# AUX_power_board_V3_3.net
KiCad netlist of a schematic drawn in EAGLE
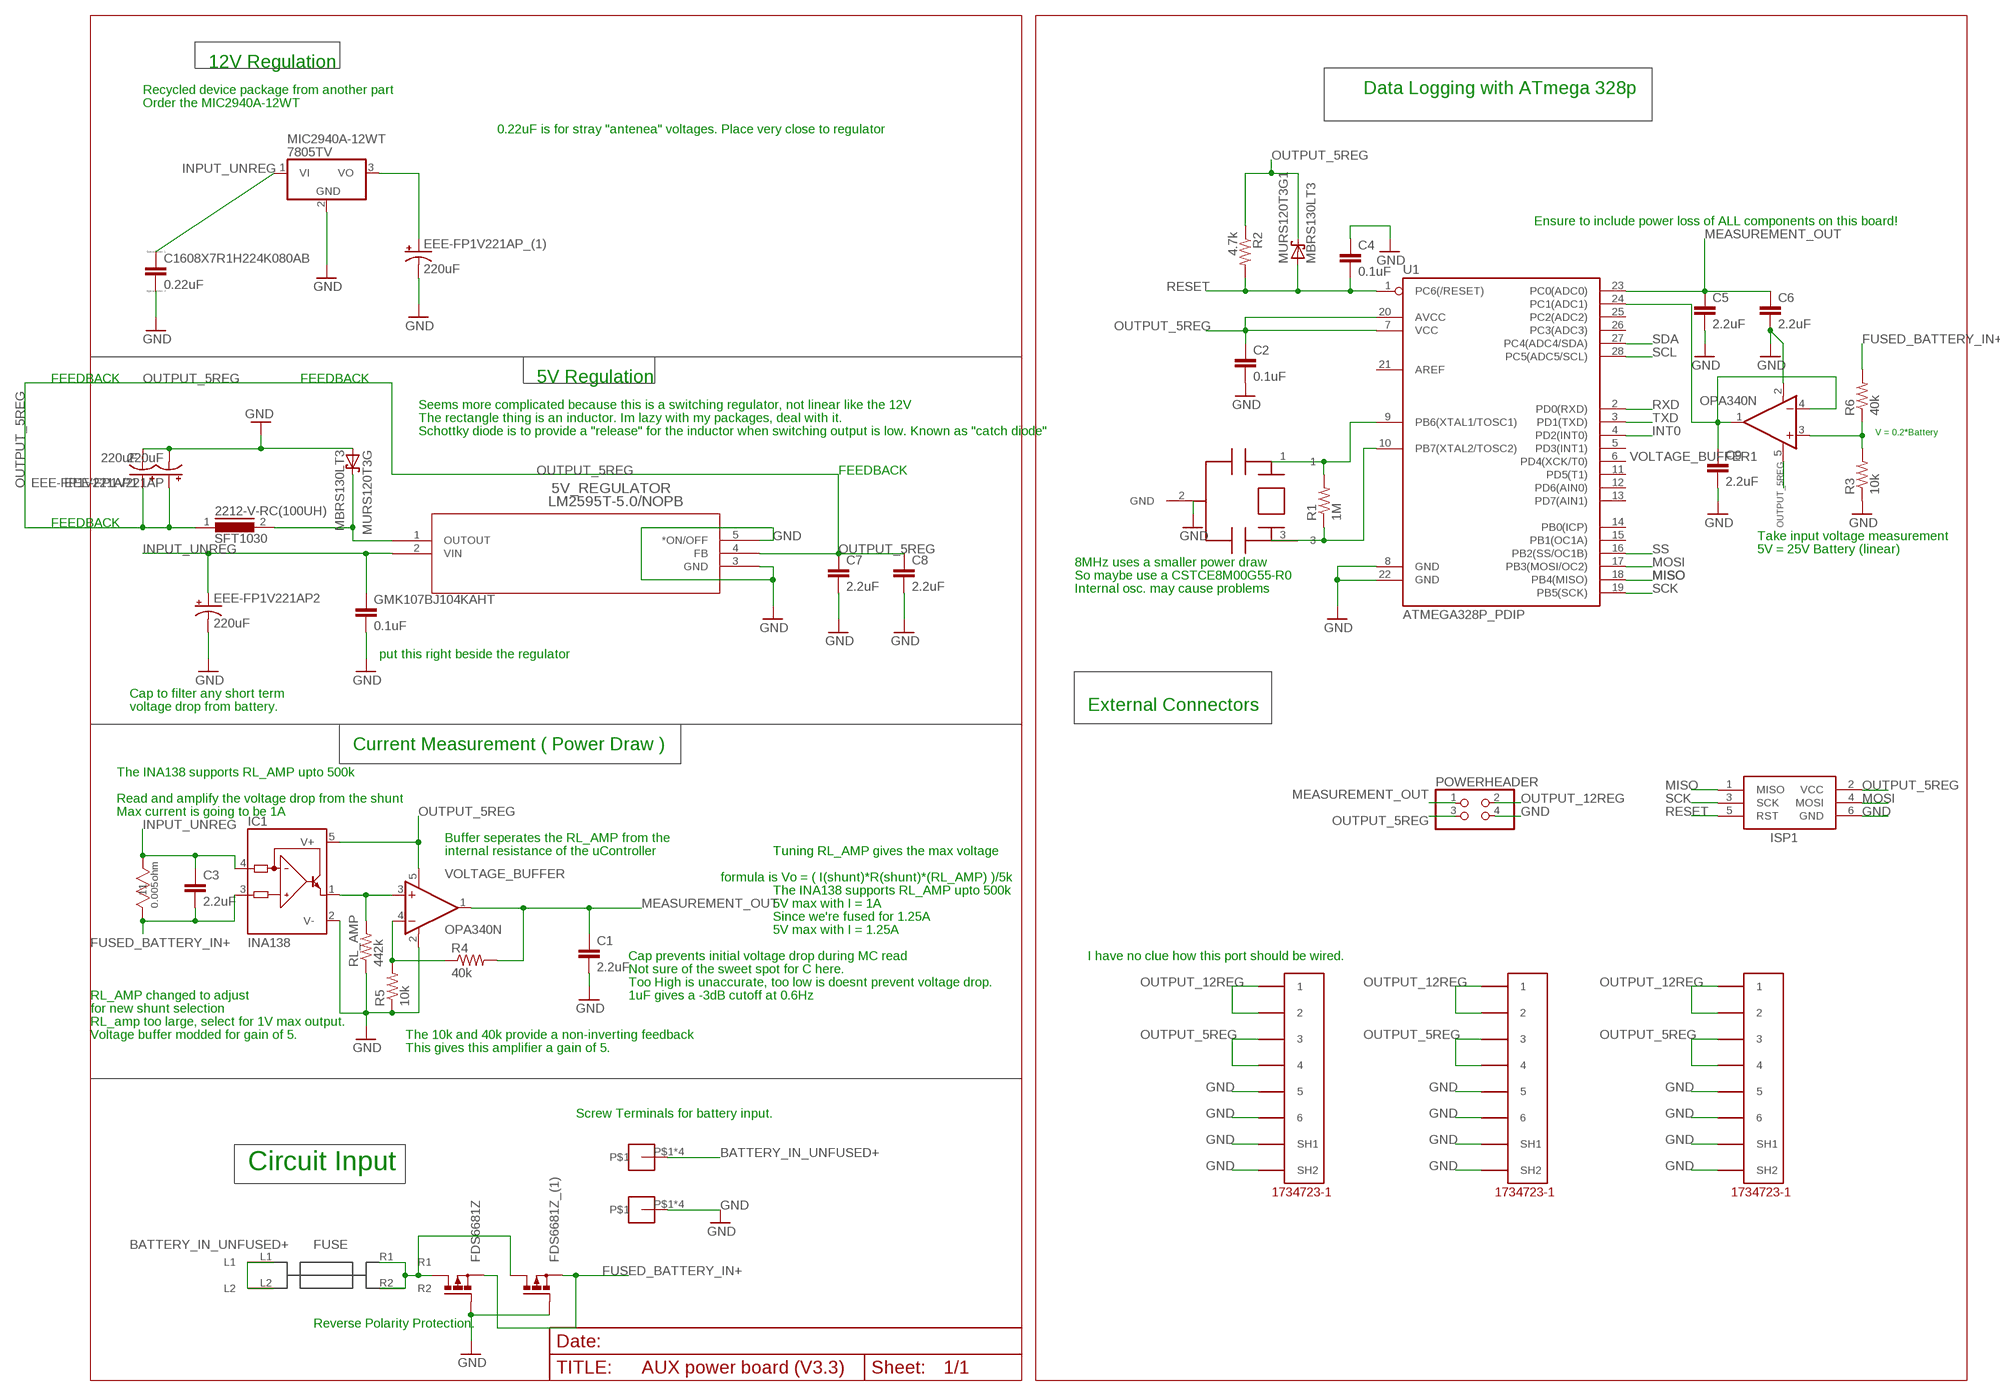
[diagram p0: schematic, sheet 1]

(export (version "E")
  (design (tool "Eeschema 10.0.6"))
  (components
    (comp (ref "5V_REGULATOR")
      (value "LM2595T-5.0/NOPB")
      (footprint "eagle-import:T05D")
      (fields
        (field (name "MANUFACTURER_PART_NUMBER") "LM2595T50")
        (field (name "COPYRIGHT") "Copyright C 2015 Accelerated Designs. All rights reserved")
      )
      (libsource (lib "eagle-import") (part "LM2595T-5.0/NOPB"))
    )
    (comp (ref "15FR005E")
      (value "15FR005E")
      (footprint "eagle-import:RES_15")
      (fields (field (name "COPYRIGHT") "Copyright C 2015 Accelerated Designs. All rights reserved"))
      (libsource (lib "eagle-import") (part "15FR005E"))
    )
    (comp (ref "2212-V-RC(100UH)")
      (value "SFT1030")
      (footprint "eagle-import:SFT1030")
      (libsource (lib "eagle-import") (part "SFT1030"))
    )
    (comp (ref "C1")
      (value "2.2uF")
      (footprint "eagle-import:C0603")
      (libsource (lib "eagle-import") (part "resistor_C-EUC0603"))
    )
    (comp (ref "C2")
      (value "0.1uF")
      (footprint "eagle-import:C0603")
      (libsource (lib "eagle-import") (part "resistor_C-EUC0603"))
    )
    (comp (ref "C3")
      (value "2.2uF")
      (footprint "eagle-import:C0603")
      (libsource (lib "eagle-import") (part "C-EUC0603"))
    )
    (comp (ref "C4")
      (value "0.1uF")
      (footprint "eagle-import:C0603")
      (libsource (lib "eagle-import") (part "C-EUC0603"))
    )
    (comp (ref "C5")
      (value "2.2uF")
      (footprint "eagle-import:C0603")
      (libsource (lib "eagle-import") (part "C-EUC0603"))
    )
    (comp (ref "C6")
      (value "2.2uF")
      (footprint "eagle-import:C0603")
      (libsource (lib "eagle-import") (part "C-EUC0603"))
    )
    (comp (ref "C7")
      (value "2.2uF")
      (footprint "eagle-import:C0603")
      (libsource (lib "eagle-import") (part "C-EUC0603"))
    )
    (comp (ref "C8")
      (value "2.2uF")
      (footprint "eagle-import:C0603")
      (libsource (lib "eagle-import") (part "C-EUC0603"))
    )
    (comp (ref "C9")
      (value "2.2uF")
      (footprint "eagle-import:C0603")
      (libsource (lib "eagle-import") (part "C-EUC0603"))
    )
    (comp (ref "C1608X7R1H224K080AB")
      (value "0.22uF")
      (footprint "eagle-import:C0603")
      (libsource (lib "eagle-import") (part "CC0603"))
    )
    (comp (ref "CSTCE8M00G55-R0")
      (value "CSTCE16M0V53-R0")
      (footprint "eagle-import:RESONATOR")
      (libsource (lib "eagle-import") (part "CSTCE16M0V53-R0"))
    )
    (comp (ref "EEE-FP1V221AP")
      (value "220uF")
      (footprint "eagle-import:175TMP-0808")
      (libsource (lib "eagle-import") (part "CPOL-US175TMP-0808"))
    )
    (comp (ref "EEE-FP1V221AP1")
      (value "220uF")
      (footprint "eagle-import:175TMP-0808")
      (libsource (lib "eagle-import") (part "CPOL-US175TMP-0808"))
    )
    (comp (ref "EEE-FP1V221AP2")
      (value "220uF")
      (footprint "eagle-import:175TMP-0808")
      (libsource (lib "eagle-import") (part "CPOL-US175TMP-0808"))
    )
    (comp (ref "EEE-FP1V221AP_(1)")
      (value "220uF")
      (footprint "eagle-import:175TMP-0808")
      (libsource (lib "eagle-import") (part "CPOL-US175TMP-0808"))
    )
    (comp (ref "FDS6681Z")
      (value "P-MOSFET-SO8")
      (footprint "eagle-import:SO-08")
      (libsource (lib "eagle-import") (part "P-MOSFET-SO8"))
    )
    (comp (ref "FDS6681Z_(1)")
      (value "P-MOSFET-SO8")
      (footprint "eagle-import:SO-08")
      (libsource (lib "eagle-import") (part "P-MOSFET-SO8"))
    )
    (comp (ref "GMK107BJ104KAHT")
      (value "0.1uF")
      (footprint "eagle-import:C0603")
      (libsource (lib "eagle-import") (part "C-EUC0603"))
    )
    (comp (ref "IC1")
      (value "INA138")
      (footprint "eagle-import:SOT23-5")
      (fields (field (name "MF") "TEXAS INSTRUMENTS") (field (name "MPN") "INA138NA/250"))
      (libsource (lib "eagle-import") (part "INA138"))
    )
    (comp (ref "ISP1")
      (value "AVRISP-6")
      (footprint "eagle-import:AVRISP")
      (libsource (lib "eagle-import") (part "AVRISP-6"))
    )
    (comp (ref "MIC2940A-12WT")
      (value "7805TV")
      (footprint "eagle-import:TO220V")
      (libsource (lib "eagle-import") (part "78TV05"))
    )
    (comp (ref "MINIBLADE")
      (value "3568")
      (footprint "eagle-import:3568")
      (libsource (lib "eagle-import") (part "3568"))
    )
    (comp (ref "MURS120T3G")
      (value "MBRS130LT3")
      (footprint "eagle-import:SMB")
      (libsource (lib "eagle-import") (part "MBRS130LT3"))
    )
    (comp (ref "MURS120T3G1")
      (value "MBRS130LT3")
      (footprint "eagle-import:SMB")
      (libsource (lib "eagle-import") (part "MBRS130LT3"))
    )
    (comp (ref "POWERHEADER")
      (value "PINHD-2X2")
      (footprint "eagle-import:2X02")
      (libsource (lib "eagle-import") (part "PINHD-2X2"))
    )
    (comp (ref "R1")
      (value "1M")
      (footprint "eagle-import:R0603")
      (libsource (lib "eagle-import") (part "R-US_R0603"))
    )
    (comp (ref "R2")
      (value "4.7k")
      (footprint "eagle-import:R0603")
      (libsource (lib "eagle-import") (part "resistor_R-US_R0603"))
    )
    (comp (ref "R3")
      (value "10k")
      (footprint "eagle-import:R0603")
      (libsource (lib "eagle-import") (part "resistor_R-US_R0603"))
    )
    (comp (ref "R4")
      (value "40k")
      (footprint "eagle-import:R0603")
      (libsource (lib "eagle-import") (part "resistor_R-US_R0603"))
    )
    (comp (ref "R5")
      (value "10k")
      (footprint "eagle-import:R0603")
      (libsource (lib "eagle-import") (part "resistor_R-US_R0603"))
    )
    (comp (ref "R6")
      (value "40k")
      (footprint "eagle-import:R0603")
      (libsource (lib "eagle-import") (part "resistor_R-US_R0603"))
    )
    (comp (ref "RL_AMP")
      (value "442k")
      (footprint "eagle-import:R0603")
      (libsource (lib "eagle-import") (part "resistor_R-US_R0603"))
    )
    (comp (ref "U$3")
      (value "5555140-6")
      (footprint "eagle-import:1734723-1_RJ11")
      (libsource (lib "eagle-import") (part "5555140-6"))
    )
    (comp (ref "U$4")
      (value "5555140-6")
      (footprint "eagle-import:1734723-1_RJ11")
      (libsource (lib "eagle-import") (part "5555140-6"))
    )
    (comp (ref "U$5")
      (value "5555140-6")
      (footprint "eagle-import:1734723-1_RJ11")
      (libsource (lib "eagle-import") (part "5555140-6"))
    )
    (comp (ref "U$6")
      (value "SCREW-8191")
      (footprint "eagle-import:SCREW-8191")
      (libsource (lib "eagle-import") (part "SCREW-8191"))
    )
    (comp (ref "U$7")
      (value "SCREW-8191")
      (footprint "eagle-import:SCREW-8191")
      (libsource (lib "eagle-import") (part "SCREW-8191"))
    )
    (comp (ref "U1")
      (value "ATMEGA328P_PDIP")
      (footprint "eagle-import:DIL28-3")
      (libsource (lib "eagle-import") (part "ATMEGA328P_PDIP"))
    )
    (comp (ref "VOLTAGE_BUFFER")
      (value "OPA340N")
      (footprint "eagle-import:SOT23-5")
      (fields (field (name "MPN") "OPA340NA/3KG4"))
      (libsource (lib "eagle-import") (part "OPA340N"))
    )
    (comp (ref "VOLTAGE_BUFFER1")
      (value "OPA340N")
      (footprint "eagle-import:SOT23-5")
      (fields (field (name "MPN") "OPA340NA/3KG4"))
      (libsource (lib "eagle-import") (part "OPA340N"))
    )
  )
  (nets
    (net (code "1") (name "/BATTERY_IN_UNFUSED+") (class "Default")
      (node (ref "MINIBLADE") (pin "L1") (pinfunction "L1_L1") (pintype "bidirectional"))
      (node (ref "MINIBLADE") (pin "L2") (pinfunction "L2_L2") (pintype "bidirectional"))
      (node (ref "U$6") (pin "P$1") (pinfunction "P$1_P$1") (pintype "bidirectional"))
      (node (ref "U$6") (pin "P$2") (pinfunction "P$1_P$2") (pintype "bidirectional"))
      (node (ref "U$6") (pin "P$3") (pinfunction "P$1_P$3") (pintype "bidirectional"))
      (node (ref "U$6") (pin "P$4") (pinfunction "P$1_P$4") (pintype "bidirectional"))
    )
    (net (code "2") (name "/FUSED_BATTERY_IN+") (class "Default")
      (node (ref "15FR005E") (pin "1") (pinfunction "11_1") (pintype "passive"))
      (node (ref "C3") (pin "2") (pinfunction "2_2") (pintype "passive"))
      (node (ref "FDS6681Z") (pin "1") (pinfunction "S_1") (pintype "passive"))
      (node (ref "FDS6681Z") (pin "2") (pinfunction "S_2") (pintype "passive"))
      (node (ref "FDS6681Z") (pin "3") (pinfunction "S_3") (pintype "passive"))
      (node (ref "FDS6681Z_(1)") (pin "1") (pinfunction "S_1") (pintype "passive"))
      (node (ref "FDS6681Z_(1)") (pin "2") (pinfunction "S_2") (pintype "passive"))
      (node (ref "FDS6681Z_(1)") (pin "3") (pinfunction "S_3") (pintype "passive"))
      (node (ref "IC1") (pin "3") (pinfunction "IN+_3") (pintype "input"))
      (node (ref "R6") (pin "2") (pinfunction "2_2") (pintype "passive"))
    )
    (net (code "3") (name "/INPUT_UNREG") (class "Default")
      (node (ref "15FR005E") (pin "2") (pinfunction "22_2") (pintype "passive"))
      (node (ref "5V_REGULATOR") (pin "2") (pinfunction "VIN_2") (pintype "input"))
      (node (ref "C1608X7R1H224K080AB") (pin "1") (pinfunction "1_1") (pintype "passive"))
      (node (ref "C3") (pin "1") (pinfunction "1_1") (pintype "passive"))
      (node (ref "EEE-FP1V221AP2") (pin "+") (pinfunction "+_+") (pintype "passive"))
      (node (ref "GMK107BJ104KAHT") (pin "1") (pinfunction "1_1") (pintype "passive"))
      (node (ref "IC1") (pin "4") (pinfunction "IN-_4") (pintype "input"))
      (node (ref "MIC2940A-12WT") (pin "1") (pinfunction "VI_1") (pintype "input"))
    )
    (net (code "4") (name "/INT0") (class "Default")
      (node (ref "U1") (pin "4") (pinfunction "PD2(INT0)_4") (pintype "bidirectional"))
    )
    (net (code "5") (name "/MEASUREMENT_OUT") (class "Default")
      (node (ref "C1") (pin "1") (pinfunction "1_1") (pintype "passive"))
      (node (ref "C5") (pin "1") (pinfunction "1_1") (pintype "passive"))
      (node (ref "C6") (pin "1") (pinfunction "1_1") (pintype "passive"))
      (node (ref "POWERHEADER") (pin "1") (pinfunction "1_1") (pintype "passive"))
      (node (ref "R4") (pin "2") (pinfunction "2_2") (pintype "passive"))
      (node (ref "U1") (pin "23") (pinfunction "PC0(ADC0)_23") (pintype "bidirectional"))
      (node (ref "VOLTAGE_BUFFER") (pin "1") (pinfunction "OUT_1") (pintype "output"))
    )
    (net (code "6") (name "/MISO") (class "Default")
      (node (ref "ISP1") (pin "1") (pinfunction "MISO_1") (pintype "input"))
      (node (ref "U1") (pin "18") (pinfunction "PB4(MISO)_18") (pintype "bidirectional"))
    )
    (net (code "7") (name "/MOSI") (class "Default")
      (node (ref "ISP1") (pin "4") (pinfunction "MOSI_4") (pintype "output"))
      (node (ref "U1") (pin "17") (pinfunction "PB3(MOSI/OC2)_17") (pintype "bidirectional"))
    )
    (net (code "8") (name "/OUTPUT_5REG") (class "Default")
      (node (ref "2212-V-RC(100UH)") (pin "1") (pinfunction "1_1") (pintype "passive"))
      (node (ref "5V_REGULATOR") (pin "4") (pinfunction "FB_4") (pintype "passive"))
      (node (ref "C2") (pin "1") (pinfunction "1_1") (pintype "passive"))
      (node (ref "C7") (pin "1") (pinfunction "1_1") (pintype "passive"))
      (node (ref "C8") (pin "1") (pinfunction "1_1") (pintype "passive"))
      (node (ref "EEE-FP1V221AP") (pin "+") (pinfunction "+_+") (pintype "passive"))
      (node (ref "EEE-FP1V221AP1") (pin "+") (pinfunction "+_+") (pintype "passive"))
      (node (ref "IC1") (pin "5") (pinfunction "V+_5") (pintype "power_in"))
      (node (ref "ISP1") (pin "2") (pinfunction "VCC_2") (pintype "power_in"))
      (node (ref "MURS120T3G1") (pin "C") (pinfunction "C_C") (pintype "passive"))
      (node (ref "POWERHEADER") (pin "3") (pinfunction "3_3") (pintype "passive"))
      (node (ref "R2") (pin "1") (pinfunction "1_1") (pintype "passive"))
      (node (ref "U$3") (pin "3") (pinfunction "3_3") (pintype "bidirectional"))
      (node (ref "U$3") (pin "4") (pinfunction "4_4") (pintype "bidirectional"))
      (node (ref "U$4") (pin "3") (pinfunction "3_3") (pintype "bidirectional"))
      (node (ref "U$4") (pin "4") (pinfunction "4_4") (pintype "bidirectional"))
      (node (ref "U$5") (pin "3") (pinfunction "3_3") (pintype "bidirectional"))
      (node (ref "U$5") (pin "4") (pinfunction "4_4") (pintype "bidirectional"))
      (node (ref "U1") (pin "20") (pinfunction "AVCC_20") (pintype "bidirectional"))
      (node (ref "U1") (pin "7") (pinfunction "VCC_7") (pintype "bidirectional"))
      (node (ref "VOLTAGE_BUFFER") (pin "5") (pinfunction "V+_5") (pintype "power_in"))
      (node (ref "VOLTAGE_BUFFER1") (pin "5") (pinfunction "V+_5") (pintype "power_in"))
    )
    (net (code "9") (name "/OUTPUT_12REG") (class "Default")
      (node (ref "EEE-FP1V221AP_(1)") (pin "+") (pinfunction "+_+") (pintype "passive"))
      (node (ref "MIC2940A-12WT") (pin "3") (pinfunction "VO_3") (pintype "passive"))
      (node (ref "POWERHEADER") (pin "2") (pinfunction "2_2") (pintype "passive"))
      (node (ref "U$3") (pin "1") (pinfunction "1_1") (pintype "bidirectional"))
      (node (ref "U$3") (pin "2") (pinfunction "2_2") (pintype "bidirectional"))
      (node (ref "U$4") (pin "1") (pinfunction "1_1") (pintype "bidirectional"))
      (node (ref "U$4") (pin "2") (pinfunction "2_2") (pintype "bidirectional"))
      (node (ref "U$5") (pin "1") (pinfunction "1_1") (pintype "bidirectional"))
      (node (ref "U$5") (pin "2") (pinfunction "2_2") (pintype "bidirectional"))
    )
    (net (code "10") (name "/RESET") (class "Default")
      (node (ref "C4") (pin "2") (pinfunction "2_2") (pintype "passive"))
      (node (ref "ISP1") (pin "5") (pinfunction "RST_5") (pintype "output"))
      (node (ref "MURS120T3G1") (pin "A") (pinfunction "A_A") (pintype "passive"))
      (node (ref "R2") (pin "2") (pinfunction "2_2") (pintype "passive"))
      (node (ref "U1") (pin "1") (pinfunction "PC6(/RESET)_1") (pintype "bidirectional"))
    )
    (net (code "11") (name "/RXD") (class "Default")
      (node (ref "U1") (pin "2") (pinfunction "PD0(RXD)_2") (pintype "bidirectional"))
    )
    (net (code "12") (name "/SCK") (class "Default")
      (node (ref "ISP1") (pin "3") (pinfunction "SCK_3") (pintype "output"))
      (node (ref "U1") (pin "19") (pinfunction "PB5(SCK)_19") (pintype "bidirectional"))
    )
    (net (code "13") (name "/SCL") (class "Default")
      (node (ref "U1") (pin "28") (pinfunction "PC5(ADC5/SCL)_28") (pintype "bidirectional"))
    )
    (net (code "14") (name "/SDA") (class "Default")
      (node (ref "U1") (pin "27") (pinfunction "PC4(ADC4/SDA)_27") (pintype "bidirectional"))
    )
    (net (code "15") (name "/SS") (class "Default")
      (node (ref "U1") (pin "16") (pinfunction "PB2(SS/OC1B)_16") (pintype "bidirectional"))
    )
    (net (code "16") (name "/TXD") (class "Default")
      (node (ref "U1") (pin "3") (pinfunction "PD1(TXD)_3") (pintype "bidirectional"))
    )
    (net (code "17") (name "GND") (class "Default")
      (node (ref "5V_REGULATOR") (pin "3") (pinfunction "GND_3") (pintype "passive"))
      (node (ref "5V_REGULATOR") (pin "5") (pinfunction "*ON/OFF_5") (pintype "passive"))
      (node (ref "C1") (pin "2") (pinfunction "2_2") (pintype "passive"))
      (node (ref "C1608X7R1H224K080AB") (pin "2") (pinfunction "2_2") (pintype "passive"))
      (node (ref "C2") (pin "2") (pinfunction "2_2") (pintype "passive"))
      (node (ref "C4") (pin "1") (pinfunction "1_1") (pintype "passive"))
      (node (ref "C5") (pin "2") (pinfunction "2_2") (pintype "passive"))
      (node (ref "C6") (pin "2") (pinfunction "2_2") (pintype "passive"))
      (node (ref "C7") (pin "2") (pinfunction "2_2") (pintype "passive"))
      (node (ref "C8") (pin "2") (pinfunction "2_2") (pintype "passive"))
      (node (ref "C9") (pin "2") (pinfunction "2_2") (pintype "passive"))
      (node (ref "CSTCE8M00G55-R0") (pin "2") (pinfunction "GND_2") (pintype "bidirectional"))
      (node (ref "EEE-FP1V221AP") (pin "-") (pinfunction "-_-") (pintype "passive"))
      (node (ref "EEE-FP1V221AP1") (pin "-") (pinfunction "-_-") (pintype "passive"))
      (node (ref "EEE-FP1V221AP2") (pin "-") (pinfunction "-_-") (pintype "passive"))
      (node (ref "EEE-FP1V221AP_(1)") (pin "-") (pinfunction "-_-") (pintype "passive"))
      (node (ref "FDS6681Z") (pin "4") (pinfunction "G_4") (pintype "passive"))
      (node (ref "FDS6681Z_(1)") (pin "4") (pinfunction "G_4") (pintype "passive"))
      (node (ref "GMK107BJ104KAHT") (pin "2") (pinfunction "2_2") (pintype "passive"))
      (node (ref "IC1") (pin "2") (pinfunction "V-_2") (pintype "power_in"))
      (node (ref "ISP1") (pin "6") (pinfunction "GND_6") (pintype "power_in"))
      (node (ref "MIC2940A-12WT") (pin "2") (pinfunction "GND_2") (pintype "passive"))
      (node (ref "MURS120T3G") (pin "A") (pinfunction "A_A") (pintype "passive"))
      (node (ref "POWERHEADER") (pin "4") (pinfunction "4_4") (pintype "passive"))
      (node (ref "R3") (pin "1") (pinfunction "1_1") (pintype "passive"))
      (node (ref "R5") (pin "1") (pinfunction "1_1") (pintype "passive"))
      (node (ref "RL_AMP") (pin "1") (pinfunction "1_1") (pintype "passive"))
      (node (ref "U$3") (pin "5") (pinfunction "5_5") (pintype "bidirectional"))
      (node (ref "U$3") (pin "6") (pinfunction "6_6") (pintype "bidirectional"))
      (node (ref "U$3") (pin "SH1") (pinfunction "SH1_SH1") (pintype "bidirectional"))
      (node (ref "U$3") (pin "SH2") (pinfunction "SH2_SH2") (pintype "bidirectional"))
      (node (ref "U$4") (pin "5") (pinfunction "5_5") (pintype "bidirectional"))
      (node (ref "U$4") (pin "6") (pinfunction "6_6") (pintype "bidirectional"))
      (node (ref "U$4") (pin "SH1") (pinfunction "SH1_SH1") (pintype "bidirectional"))
      (node (ref "U$4") (pin "SH2") (pinfunction "SH2_SH2") (pintype "bidirectional"))
      (node (ref "U$5") (pin "5") (pinfunction "5_5") (pintype "bidirectional"))
      (node (ref "U$5") (pin "6") (pinfunction "6_6") (pintype "bidirectional"))
      (node (ref "U$5") (pin "SH1") (pinfunction "SH1_SH1") (pintype "bidirectional"))
      (node (ref "U$5") (pin "SH2") (pinfunction "SH2_SH2") (pintype "bidirectional"))
      (node (ref "U$7") (pin "P$1") (pinfunction "P$1_P$1") (pintype "bidirectional"))
      (node (ref "U$7") (pin "P$2") (pinfunction "P$1_P$2") (pintype "bidirectional"))
      (node (ref "U$7") (pin "P$3") (pinfunction "P$1_P$3") (pintype "bidirectional"))
      (node (ref "U$7") (pin "P$4") (pinfunction "P$1_P$4") (pintype "bidirectional"))
      (node (ref "U1") (pin "22") (pinfunction "GND_22") (pintype "bidirectional"))
      (node (ref "U1") (pin "8") (pinfunction "GND_8") (pintype "bidirectional"))
      (node (ref "VOLTAGE_BUFFER") (pin "2") (pinfunction "V-_2") (pintype "power_in"))
      (node (ref "VOLTAGE_BUFFER1") (pin "2") (pinfunction "V-_2") (pintype "power_in"))
    )
    (net (code "18") (name "Net-(5V_REGULATOR-OUTOUT)") (class "Default")
      (node (ref "2212-V-RC(100UH)") (pin "2") (pinfunction "2_2") (pintype "passive"))
      (node (ref "5V_REGULATOR") (pin "1") (pinfunction "OUTOUT_1") (pintype "output"))
      (node (ref "MURS120T3G") (pin "C") (pinfunction "C_C") (pintype "passive"))
    )
    (net (code "19") (name "Net-(FDS6681Z-D-Pad5)") (class "Default")
      (node (ref "FDS6681Z") (pin "5") (pinfunction "D_5") (pintype "passive"))
      (node (ref "FDS6681Z") (pin "6") (pinfunction "D_6") (pintype "passive"))
      (node (ref "FDS6681Z") (pin "7") (pinfunction "D_7") (pintype "passive"))
      (node (ref "FDS6681Z") (pin "8") (pinfunction "D_8") (pintype "passive"))
      (node (ref "FDS6681Z_(1)") (pin "5") (pinfunction "D_5") (pintype "passive"))
      (node (ref "FDS6681Z_(1)") (pin "6") (pinfunction "D_6") (pintype "passive"))
      (node (ref "FDS6681Z_(1)") (pin "7") (pinfunction "D_7") (pintype "passive"))
      (node (ref "FDS6681Z_(1)") (pin "8") (pinfunction "D_8") (pintype "passive"))
      (node (ref "MINIBLADE") (pin "R1") (pinfunction "R1_R1") (pintype "bidirectional"))
      (node (ref "MINIBLADE") (pin "R2") (pinfunction "R2_R2") (pintype "bidirectional"))
    )
    (net (code "20") (name "Net-(IC1-OUT)") (class "Default")
      (node (ref "IC1") (pin "1") (pinfunction "OUT_1") (pintype "output"))
      (node (ref "RL_AMP") (pin "2") (pinfunction "2_2") (pintype "passive"))
      (node (ref "VOLTAGE_BUFFER") (pin "3") (pinfunction "+IN_3") (pintype "input"))
    )
    (net (code "21") (name "Net-(U1-PB6(XTAL1{slash}TOSC1))") (class "Default")
      (node (ref "CSTCE8M00G55-R0") (pin "1") (pinfunction "1_1") (pintype "bidirectional"))
      (node (ref "R1") (pin "2") (pinfunction "2_2") (pintype "passive"))
      (node (ref "U1") (pin "9") (pinfunction "PB6(XTAL1/TOSC1)_9") (pintype "bidirectional"))
    )
    (net (code "22") (name "Net-(U1-PB7(XTAL2{slash}TOSC2))") (class "Default")
      (node (ref "CSTCE8M00G55-R0") (pin "3") (pinfunction "3_3") (pintype "bidirectional"))
      (node (ref "R1") (pin "1") (pinfunction "1_1") (pintype "passive"))
      (node (ref "U1") (pin "10") (pinfunction "PB7(XTAL2/TOSC2)_10") (pintype "bidirectional"))
    )
    (net (code "23") (name "Net-(U1-PC1(ADC1))") (class "Default")
      (node (ref "C9") (pin "1") (pinfunction "1_1") (pintype "passive"))
      (node (ref "U1") (pin "24") (pinfunction "PC1(ADC1)_24") (pintype "bidirectional"))
      (node (ref "VOLTAGE_BUFFER1") (pin "1") (pinfunction "OUT_1") (pintype "output"))
      (node (ref "VOLTAGE_BUFFER1") (pin "4") (pinfunction "-IN_4") (pintype "input"))
    )
    (net (code "24") (name "Net-(VOLTAGE_BUFFER--IN)") (class "Default")
      (node (ref "R4") (pin "1") (pinfunction "1_1") (pintype "passive"))
      (node (ref "R5") (pin "2") (pinfunction "2_2") (pintype "passive"))
      (node (ref "VOLTAGE_BUFFER") (pin "4") (pinfunction "-IN_4") (pintype "input"))
    )
    (net (code "25") (name "Net-(VOLTAGE_BUFFER1-+IN)") (class "Default")
      (node (ref "R3") (pin "2") (pinfunction "2_2") (pintype "passive"))
      (node (ref "R6") (pin "1") (pinfunction "1_1") (pintype "passive"))
      (node (ref "VOLTAGE_BUFFER1") (pin "3") (pinfunction "+IN_3") (pintype "input"))
    )
    (net (code "26") (name "unconnected-(U1-AREF-Pad21)") (class "Default")
      (node (ref "U1") (pin "21") (pinfunction "AREF_21") (pintype "bidirectional"))
    )
    (net (code "27") (name "unconnected-(U1-PB0(ICP)-Pad14)") (class "Default")
      (node (ref "U1") (pin "14") (pinfunction "PB0(ICP)_14") (pintype "bidirectional"))
    )
    (net (code "28") (name "unconnected-(U1-PB1(OC1A)-Pad15)") (class "Default")
      (node (ref "U1") (pin "15") (pinfunction "PB1(OC1A)_15") (pintype "bidirectional"))
    )
    (net (code "29") (name "unconnected-(U1-PC2(ADC2)-Pad25)") (class "Default")
      (node (ref "U1") (pin "25") (pinfunction "PC2(ADC2)_25") (pintype "bidirectional"))
    )
    (net (code "30") (name "unconnected-(U1-PC3(ADC3)-Pad26)") (class "Default")
      (node (ref "U1") (pin "26") (pinfunction "PC3(ADC3)_26") (pintype "bidirectional"))
    )
    (net (code "31") (name "unconnected-(U1-PD3(INT1)-Pad5)") (class "Default")
      (node (ref "U1") (pin "5") (pinfunction "PD3(INT1)_5") (pintype "bidirectional"))
    )
    (net (code "32") (name "unconnected-(U1-PD4(XCK{slash}T0)-Pad6)") (class "Default")
      (node (ref "U1") (pin "6") (pinfunction "PD4(XCK/T0)_6") (pintype "bidirectional"))
    )
    (net (code "33") (name "unconnected-(U1-PD5(T1)-Pad11)") (class "Default")
      (node (ref "U1") (pin "11") (pinfunction "PD5(T1)_11") (pintype "bidirectional"))
    )
    (net (code "34") (name "unconnected-(U1-PD6(AIN0)-Pad12)") (class "Default")
      (node (ref "U1") (pin "12") (pinfunction "PD6(AIN0)_12") (pintype "bidirectional"))
    )
    (net (code "35") (name "unconnected-(U1-PD7(AIN1)-Pad13)") (class "Default")
      (node (ref "U1") (pin "13") (pinfunction "PD7(AIN1)_13") (pintype "bidirectional"))
    )
  )
)
